# SensorRotacaoMotor.net
KiCad netlist of a schematic drawn in Altium Designer
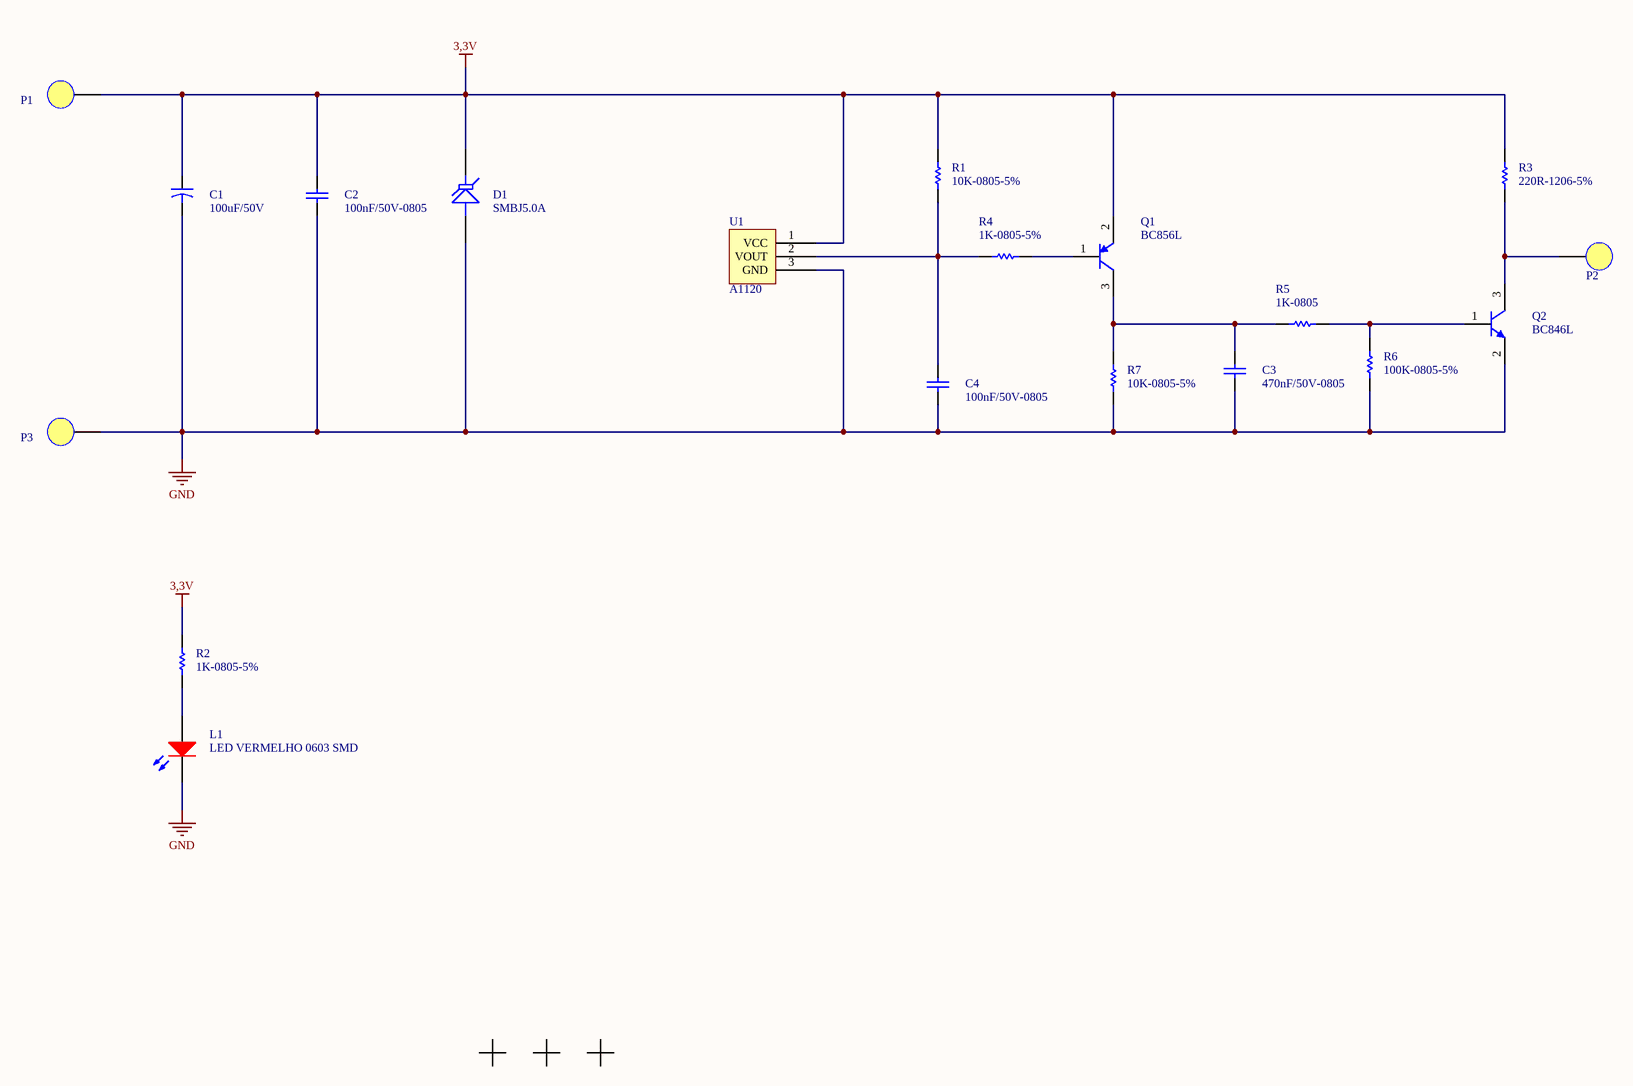
[diagram p0: SensorRotacaoMotor.SchDoc]

(export (version "E")
  (design (tool "Eeschema 10.0.6"))
  (components
    (comp (ref "C1")
      (value "100uF/50V")
      (footprint "CAP POL 8x12mm")
      (libsource (lib "AquinoLib") (part "100uF/50V"))
    )
    (comp (ref "C2")
      (value "100nF/50V-0805")
      (footprint "0805-REVISADO ONDA")
      (libsource (lib "AquinoLib") (part "100nF/50-0805-NPO"))
    )
    (comp (ref "C3")
      (value "470nF/50V-0805")
      (footprint "0805-REVISADO ONDA")
      (description "100nF/50V-0805")
      (libsource (lib "AquinoLib") (part "100nF/50-0805-NPO"))
    )
    (comp (ref "C4")
      (value "100nF/50V-0805")
      (footprint "0805-REVISADO ONDA")
      (libsource (lib "AquinoLib") (part "100nF/50-0805-NPO"))
    )
    (comp (ref "D1")
      (value "SMBJ5.0A")
      (footprint "DO-214AA")
      (libsource (lib "AquinoLib") (part "SMBJ5.0A"))
    )
    (comp (ref "FD1")
      (value "FID")
      (footprint "FIDUCIAL")
      (libsource (lib "ChaveDigital3") (part "FIDUCIAL"))
    )
    (comp (ref "FD2")
      (value "FID")
      (footprint "FIDUCIAL")
      (libsource (lib "ChaveDigital3") (part "FIDUCIAL"))
    )
    (comp (ref "FD3")
      (value "FID")
      (footprint "FIDUCIAL")
      (libsource (lib "ChaveDigital3") (part "FIDUCIAL"))
    )
    (comp (ref "L1")
      (value "LED VERMELHO 0603 SMD")
      (footprint "LED 0805 - REVISADO ONDA")
      (libsource (lib "AquinoLib") (part "LED VERMELHO 0603 SMD"))
    )
    (comp (ref "P1") (value "PAD") (footprint "PAD 3,5") (libsource (lib "ChaveDigital3") (part "PAD")))
    (comp (ref "P2") (value "PAD") (footprint "PAD 3,5") (libsource (lib "ChaveDigital3") (part "PAD")))
    (comp (ref "P3") (value "PAD") (footprint "PAD 3,5") (libsource (lib "ChaveDigital3") (part "PAD")))
    (comp (ref "Q1")
      (value "BC856L")
      (footprint "SOT23 - REVISADO ONDA")
      (libsource (lib "AquinoLib") (part "BC856L"))
    )
    (comp (ref "Q2")
      (value "BC846L")
      (footprint "SOT23 - REVISADO ONDA")
      (libsource (lib "AquinoLib") (part "BC846"))
    )
    (comp (ref "R1")
      (value "10K-0805-5%")
      (footprint "0805-REVISADO ONDA")
      (libsource (lib "AquinoLib") (part "10K-0805-5%"))
    )
    (comp (ref "R2")
      (value "1K-0805-5%")
      (footprint "0805-REVISADO ONDA")
      (libsource (lib "AquinoLib") (part "1K-0805-5%"))
    )
    (comp (ref "R3")
      (value "220R-1206-5%")
      (footprint "1206-REVISADO ONDA")
      (description "10K-0805-5%")
      (libsource (lib "AquinoLib") (part "10K-0805-5%"))
    )
    (comp (ref "R4")
      (value "1K-0805-5%")
      (footprint "0805-REVISADO ONDA")
      (libsource (lib "AquinoLib") (part "1K-0805-5%"))
    )
    (comp (ref "R5")
      (value "1K-0805")
      (footprint "0805-REVISADO ONDA")
      (description "10K-0805-5%")
      (libsource (lib "AquinoLib") (part "10K-0805-5%"))
    )
    (comp (ref "R6")
      (value "100K-0805-5%")
      (footprint "0805-REVISADO ONDA")
      (description "10K-0805-5%")
      (libsource (lib "AquinoLib") (part "10K-0805-5%"))
    )
    (comp (ref "R7")
      (value "10K-0805-5%")
      (footprint "0805-REVISADO ONDA")
      (libsource (lib "AquinoLib") (part "10K-0805-5%"))
    )
    (comp (ref "U1")
      (value "A1120")
      (footprint "SOT23 - REVISADO ONDA")
      (libsource (lib "AquinoLib") (part "A1120"))
    )
  )
  (nets
    (net (code "1") (name "3,3V") (class "Default")
      (node (ref "C1") (pin "1") (pinfunction "1_1") (pintype "passive"))
      (node (ref "C2") (pin "2") (pinfunction "2_2") (pintype "passive"))
      (node (ref "D1") (pin "2") (pinfunction "K_2") (pintype "passive"))
      (node (ref "P1") (pin "1") (pinfunction "1_1") (pintype "passive"))
      (node (ref "Q1") (pin "2") (pinfunction "E_2") (pintype "passive"))
      (node (ref "R1") (pin "2") (pinfunction "2_2") (pintype "passive"))
      (node (ref "R2") (pin "2") (pinfunction "2_2") (pintype "passive"))
      (node (ref "R3") (pin "2") (pinfunction "2_2") (pintype "passive"))
      (node (ref "U1") (pin "1") (pinfunction "VCC_1") (pintype "passive"))
    )
    (net (code "2") (name "GND") (class "Default")
      (node (ref "C1") (pin "2") (pinfunction "2_2") (pintype "passive"))
      (node (ref "C2") (pin "1") (pinfunction "1_1") (pintype "passive"))
      (node (ref "C3") (pin "1") (pinfunction "1_1") (pintype "passive"))
      (node (ref "C4") (pin "1") (pinfunction "1_1") (pintype "passive"))
      (node (ref "D1") (pin "1") (pinfunction "A_1") (pintype "passive"))
      (node (ref "L1") (pin "2") (pinfunction "K_2") (pintype "passive"))
      (node (ref "P3") (pin "1") (pinfunction "1_1") (pintype "passive"))
      (node (ref "Q2") (pin "2") (pinfunction "E_2") (pintype "passive"))
      (node (ref "R6") (pin "2") (pinfunction "2_2") (pintype "passive"))
      (node (ref "R7") (pin "1") (pinfunction "1_1") (pintype "passive"))
      (node (ref "U1") (pin "3") (pinfunction "GND_3") (pintype "passive"))
    )
    (net (code "3") (name "Net-(L1-A)") (class "Default")
      (node (ref "L1") (pin "1") (pinfunction "A_1") (pintype "passive"))
      (node (ref "R2") (pin "1") (pinfunction "1_1") (pintype "passive"))
    )
    (net (code "4") (name "Net-(Q1-B)") (class "Default")
      (node (ref "Q1") (pin "1") (pinfunction "B_1") (pintype "passive"))
      (node (ref "R4") (pin "1") (pinfunction "1_1") (pintype "passive"))
    )
    (net (code "5") (name "Net-(Q1-C)") (class "Default")
      (node (ref "C3") (pin "2") (pinfunction "2_2") (pintype "passive"))
      (node (ref "Q1") (pin "3") (pinfunction "C_3") (pintype "passive"))
      (node (ref "R5") (pin "2") (pinfunction "2_2") (pintype "passive"))
      (node (ref "R7") (pin "2") (pinfunction "2_2") (pintype "passive"))
    )
    (net (code "6") (name "Net-(Q2-B)") (class "Default")
      (node (ref "Q2") (pin "1") (pinfunction "B_1") (pintype "passive"))
      (node (ref "R5") (pin "1") (pinfunction "1_1") (pintype "passive"))
      (node (ref "R6") (pin "1") (pinfunction "1_1") (pintype "passive"))
    )
    (net (code "7") (name "Net-(Q2-C)") (class "Default")
      (node (ref "P2") (pin "1") (pinfunction "1_1") (pintype "passive"))
      (node (ref "Q2") (pin "3") (pinfunction "C_3") (pintype "passive"))
      (node (ref "R3") (pin "1") (pinfunction "1_1") (pintype "passive"))
    )
    (net (code "8") (name "Net-(U1-VOUT)") (class "Default")
      (node (ref "C4") (pin "2") (pinfunction "2_2") (pintype "passive"))
      (node (ref "R1") (pin "1") (pinfunction "1_1") (pintype "passive"))
      (node (ref "R4") (pin "2") (pinfunction "2_2") (pintype "passive"))
      (node (ref "U1") (pin "2") (pinfunction "VOUT_2") (pintype "passive"))
    )
  )
)
